# RTC.net
KiCad netlist of a schematic drawn in Altium Designer
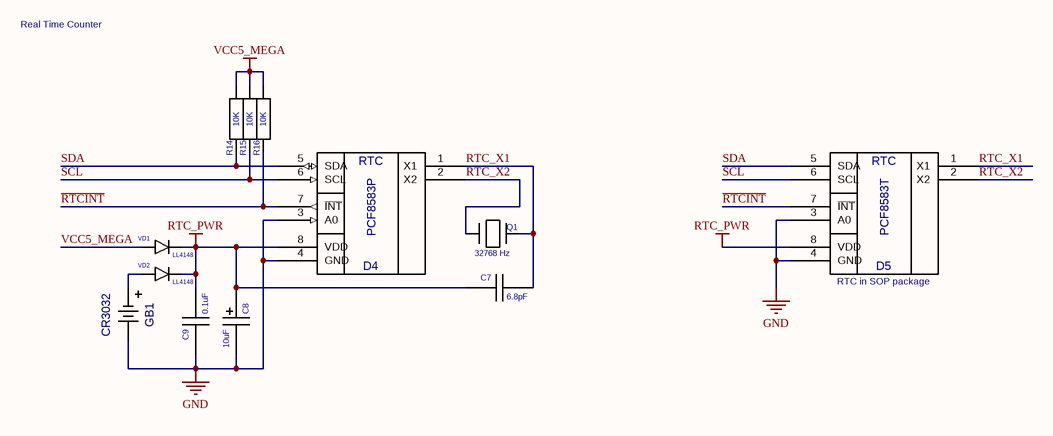
[diagram p0: RTC.SchDoc]

(export (version "E")
  (design (tool "Eeschema 10.0.6"))
  (components
    (comp (ref "C7")
      (value "6.8pF")
      (footprint "C-CHIP")
      (description "CAPCHIP")
      (libsource (lib "*") (part "CAPCHIP"))
    )
    (comp (ref "C8")
      (value "10uF")
      (footprint "EC-CHIP")
      (description "ECAPCHIP")
      (libsource (lib "*") (part "ECAPCHIP"))
    )
    (comp (ref "C9")
      (value "0.1uF")
      (footprint "C-CHIP")
      (description "CAPCHIP")
      (libsource (lib "*") (part "CAPCHIP"))
    )
    (comp (ref "D4") (value "PCF8583P") (footprint "DIP8") (libsource (lib "*") (part "PCF8583P")))
    (comp (ref "D5") (value "PCF8583T") (footprint "PCF8583T") (libsource (lib "*") (part "PCF8583T")))
    (comp (ref "GB1")
      (value "CR3032")
      (footprint "BAT")
      (description "BAT")
      (libsource (lib "*") (part "BAT"))
    )
    (comp (ref "Q1")
      (value "32768 Hz")
      (footprint "32768")
      (description "QUARTZ32768")
      (libsource (lib "*") (part "QUARTZ32768"))
    )
    (comp (ref "R14")
      (value "10K")
      (footprint "R-CHIP")
      (description "RESCHIP")
      (libsource (lib "*") (part "RESCHIP"))
    )
    (comp (ref "R15")
      (value "10K")
      (footprint "R-CHIP")
      (description "RESCHIP")
      (libsource (lib "*") (part "RESCHIP"))
    )
    (comp (ref "R16")
      (value "10K")
      (footprint "R-CHIP")
      (description "RESCHIP")
      (libsource (lib "*") (part "RESCHIP"))
    )
    (comp (ref "VD1") (value "LL4148") (footprint "LL4148") (libsource (lib "*") (part "LL4148")))
    (comp (ref "VD2") (value "LL4148") (footprint "LL4148") (libsource (lib "*") (part "LL4148")))
  )
  (nets
    (net (code "1") (name "/RTC_X1") (class "Default")
      (node (ref "C7") (pin "2") (pinfunction "2_2") (pintype "passive"))
      (node (ref "D4") (pin "1") (pinfunction "X1_1") (pintype "passive"))
      (node (ref "D5") (pin "1") (pinfunction "X1_1") (pintype "passive"))
      (node (ref "Q1") (pin "1") (pintype "passive"))
    )
    (net (code "2") (name "/RTC_X2") (class "Default")
      (node (ref "D4") (pin "2") (pinfunction "X2_2") (pintype "passive"))
      (node (ref "D5") (pin "2") (pinfunction "X2_2") (pintype "passive"))
      (node (ref "Q1") (pin "2") (pintype "passive"))
    )
    (net (code "3") (name "/SCL") (class "Default")
      (node (ref "D4") (pin "6") (pinfunction "SCL_6") (pintype "input"))
      (node (ref "D5") (pin "6") (pinfunction "SCL_6") (pintype "passive"))
      (node (ref "R15") (pin "2") (pinfunction "i/o1_2") (pintype "passive"))
    )
    (net (code "4") (name "/SDA") (class "Default")
      (node (ref "D4") (pin "5") (pinfunction "SDA_5") (pintype "bidirectional"))
      (node (ref "D5") (pin "5") (pinfunction "SDA_5") (pintype "passive"))
      (node (ref "R14") (pin "2") (pinfunction "i/o1_2") (pintype "passive"))
    )
    (net (code "5") (name "/~{RTCINT}") (class "Default")
      (node (ref "D4") (pin "7") (pinfunction "~{INT}_7") (pintype "output"))
      (node (ref "D5") (pin "7") (pinfunction "~{INT}_7") (pintype "passive"))
      (node (ref "R16") (pin "2") (pinfunction "i/o1_2") (pintype "passive"))
    )
    (net (code "6") (name "GND") (class "Default")
      (node (ref "C8") (pin "2") (pintype "passive"))
      (node (ref "C9") (pin "1") (pinfunction "1_1") (pintype "passive"))
      (node (ref "D4") (pin "3") (pinfunction "A0_3") (pintype "input"))
      (node (ref "D4") (pin "4") (pinfunction "GND_4") (pintype "power_in"))
      (node (ref "D5") (pin "3") (pinfunction "A0_3") (pintype "passive"))
      (node (ref "D5") (pin "4") (pinfunction "GND_4") (pintype "passive"))
      (node (ref "GB1") (pin "2") (pinfunction "MINUS_2") (pintype "passive"))
      (node (ref "Q1") (pin "3") (pinfunction "GND_3") (pintype "power_in"))
    )
    (net (code "7") (name "Net-(GB1-PLUS)") (class "Default")
      (node (ref "GB1") (pin "1") (pinfunction "PLUS_1") (pintype "passive"))
      (node (ref "VD2") (pin "1") (pinfunction "A_1") (pintype "passive"))
    )
    (net (code "8") (name "RTC_PWR") (class "Default")
      (node (ref "C7") (pin "1") (pinfunction "1_1") (pintype "passive"))
      (node (ref "C8") (pin "1") (pintype "passive"))
      (node (ref "C9") (pin "2") (pinfunction "2_2") (pintype "passive"))
      (node (ref "D4") (pin "8") (pinfunction "VDD_8") (pintype "power_in"))
      (node (ref "D5") (pin "8") (pinfunction "VDD_8") (pintype "passive"))
      (node (ref "VD1") (pin "2") (pinfunction "C_2") (pintype "passive"))
      (node (ref "VD2") (pin "2") (pinfunction "C_2") (pintype "passive"))
    )
    (net (code "9") (name "VCC5_MEGA") (class "Default")
      (node (ref "R14") (pin "1") (pinfunction "i/o_1") (pintype "passive"))
      (node (ref "R15") (pin "1") (pinfunction "i/o_1") (pintype "passive"))
      (node (ref "R16") (pin "1") (pinfunction "i/o_1") (pintype "passive"))
      (node (ref "VD1") (pin "1") (pinfunction "A_1") (pintype "passive"))
    )
  )
)
